# Sonic_Sandbox.net
KiCad netlist of a schematic drawn in Altium Designer
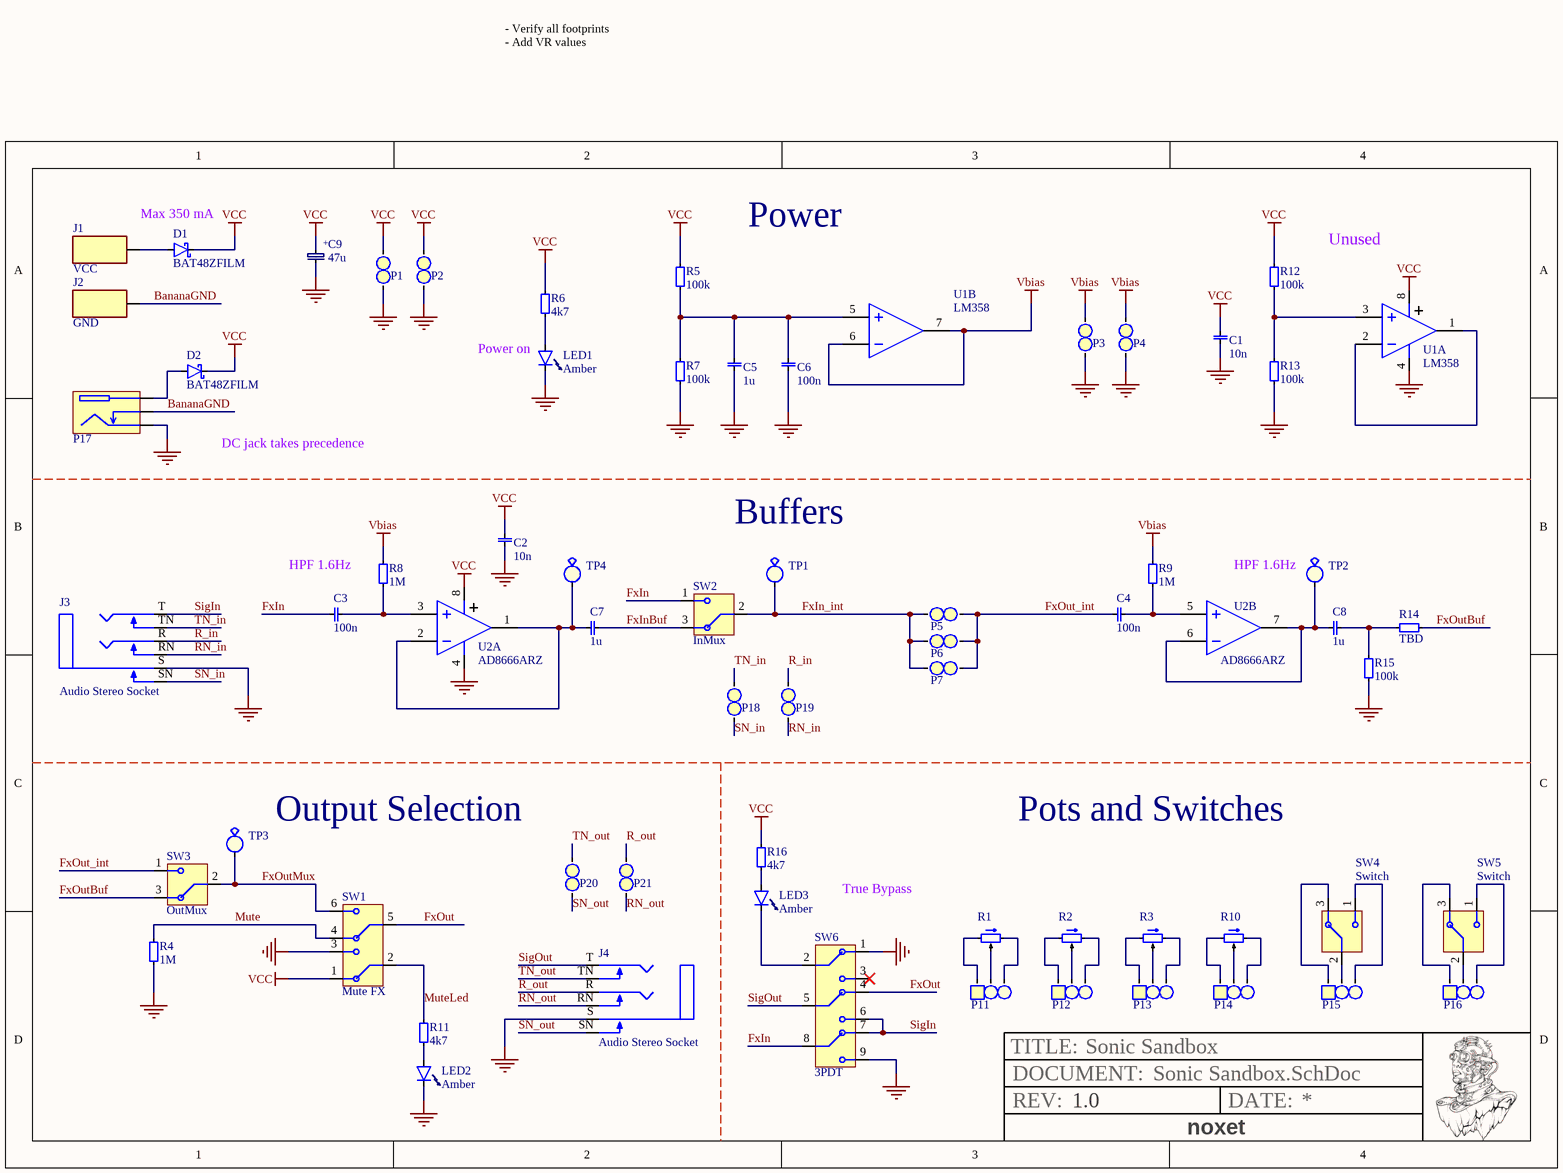
[diagram p0: Sonic Sandbox.SchDoc]

(export (version "E")
  (design (tool "Eeschema 10.0.6"))
  (components
    (comp (ref "C1")
      (value "10n")
      (footprint "0805, cap")
      (fields (field (name "Comment") "0805, capacitor"))
      (libsource (lib "jclib") (part "0805, capacitor"))
    )
    (comp (ref "C2")
      (value "10n")
      (footprint "0805, cap")
      (fields (field (name "Comment") "0805, capacitor"))
      (libsource (lib "jclib") (part "0805, capacitor"))
    )
    (comp (ref "C3")
      (value "100n")
      (footprint "0805, cap")
      (fields (field (name "Comment") "0805, capacitor"))
      (libsource (lib "jclib") (part "0805, capacitor"))
    )
    (comp (ref "C4")
      (value "100n")
      (footprint "0805, cap")
      (fields (field (name "Comment") "0805, capacitor"))
      (libsource (lib "jclib") (part "0805, capacitor"))
    )
    (comp (ref "C5")
      (value "1u")
      (footprint "0805, cap")
      (fields (field (name "Comment") "0805, capacitor"))
      (libsource (lib "jclib") (part "0805, capacitor"))
    )
    (comp (ref "C6")
      (value "100n")
      (footprint "0805, cap")
      (fields (field (name "Comment") "0805, capacitor"))
      (libsource (lib "jclib") (part "0805, capacitor"))
    )
    (comp (ref "C7")
      (value "1u")
      (footprint "0805, cap")
      (fields (field (name "Comment") "0805, capacitor"))
      (libsource (lib "jclib") (part "0805, capacitor"))
    )
    (comp (ref "C8")
      (value "1u")
      (footprint "0805, cap")
      (fields (field (name "Comment") "0805, capacitor"))
      (libsource (lib "jclib") (part "0805, capacitor"))
    )
    (comp (ref "C9")
      (value "47u")
      (footprint "Cap, SMD, Polar, 5.3x5.3mm")
      (description "Capacitor TH 2mm")
      (fields (field (name "Comment") "Capacitor, TH 2mm"))
      (libsource (lib "jclib") (part "Capacitor, TH 2mm"))
    )
    (comp (ref "D1")
      (value "BAT48ZFILM")
      (footprint "SOD123")
      (description "Rectifier Diode, Schottky, 1 Phase, 1 Element, 0.35A, 40V V(RRM), Silicon")
      (fields (field (name "MANUFACTURER") "STMicroelectronics"))
      (libsource (lib "jclib") (part "BAT48ZFILM"))
    )
    (comp (ref "D2")
      (value "BAT48ZFILM")
      (footprint "SOD123")
      (description "Rectifier Diode, Schottky, 1 Phase, 1 Element, 0.35A, 40V V(RRM), Silicon")
      (fields (field (name "MANUFACTURER") "STMicroelectronics"))
      (libsource (lib "jclib") (part "BAT48ZFILM"))
    )
    (comp (ref "J1")
      (value "VCC")
      (footprint "Banana Conn VCC")
      (description "Banana Connector 571-0100")
      (fields
        (field (name "MANUFACTURER_PART_NUMBER") "571-0100")
        (field (name "MOUSER PART NUMBER") "164-6218")
      )
      (libsource (lib "jclib") (part "Banana conn"))
    )
    (comp (ref "J2")
      (value "GND")
      (footprint "Banana Conn GND")
      (description "Banana Connector 571-0100")
      (fields
        (field (name "MANUFACTURER_PART_NUMBER") "571-0100")
        (field (name "MOUSER PART NUMBER") "164-6218")
      )
      (libsource (lib "jclib") (part "Banana conn"))
    )
    (comp (ref "J3")
      (value "Audio Stereo Socket")
      (footprint "6.3mm Audio Socket PCB")
      (libsource (lib "") (part "6.3mm Audio Socket_1"))
    )
    (comp (ref "J4")
      (value "Audio Stereo Socket")
      (footprint "6.3mm Audio Socket PCB")
      (libsource (lib "jclib") (part "6.3mm Audio Socket"))
    )
    (comp (ref "LED1") (value "Amber") (footprint "0805_led") (libsource (lib "jclib") (part "0805, LED")))
    (comp (ref "LED2") (value "Amber") (footprint "0805_led") (libsource (lib "jclib") (part "0805, LED")))
    (comp (ref "LED3") (value "Amber") (footprint "0805_led") (libsource (lib "jclib") (part "0805, LED")))
    (comp (ref "P1")
      (value "1x2 Pin Heade Straight")
      (footprint "padtwo_L")
      (description "2.54 mm, TH")
      (libsource (lib "jclib") (part "1x2 Pin Heade Straight"))
    )
    (comp (ref "P2")
      (value "1x2 Pin Heade Straight")
      (footprint "padtwo_L")
      (description "2.54 mm, TH")
      (libsource (lib "jclib") (part "1x2 Pin Heade Straight"))
    )
    (comp (ref "P3")
      (value "1x2 Pin Heade Straight")
      (footprint "padtwo_L")
      (description "2.54 mm, TH")
      (libsource (lib "jclib") (part "1x2 Pin Heade Straight"))
    )
    (comp (ref "P4")
      (value "1x2 Pin Heade Straight")
      (footprint "padtwo_L")
      (description "2.54 mm, TH")
      (libsource (lib "jclib") (part "1x2 Pin Heade Straight"))
    )
    (comp (ref "P5")
      (value "1x2 Pin Heade Straight")
      (footprint "padtwo_L")
      (description "2.54 mm, TH")
      (libsource (lib "jclib") (part "1x2 Pin Heade Straight"))
    )
    (comp (ref "P6")
      (value "1x2 Pin Heade Straight")
      (footprint "padtwo_L")
      (description "2.54 mm, TH")
      (libsource (lib "jclib") (part "1x2 Pin Heade Straight"))
    )
    (comp (ref "P7")
      (value "1x2 Pin Heade Straight")
      (footprint "padtwo_L")
      (description "2.54 mm, TH")
      (libsource (lib "jclib") (part "1x2 Pin Heade Straight"))
    )
    (comp (ref "P11")
      (value "1x3 Pin Header")
      (footprint "padThree_L")
      (description "2.54 mm")
      (libsource (lib "jclib") (part "1x3 Pin Header"))
    )
    (comp (ref "P12")
      (value "1x3 Pin Header")
      (footprint "padThree_L")
      (description "2.54 mm")
      (libsource (lib "jclib") (part "1x3 Pin Header"))
    )
    (comp (ref "P13")
      (value "1x3 Pin Header")
      (footprint "padThree_L")
      (description "2.54 mm")
      (libsource (lib "jclib") (part "1x3 Pin Header"))
    )
    (comp (ref "P14")
      (value "1x3 Pin Header")
      (footprint "padThree_L")
      (description "2.54 mm")
      (libsource (lib "jclib") (part "1x3 Pin Header"))
    )
    (comp (ref "P15")
      (value "1x3 Pin Header")
      (footprint "padThree_L")
      (description "2.54 mm")
      (libsource (lib "jclib") (part "1x3 Pin Header"))
    )
    (comp (ref "P16")
      (value "1x3 Pin Header")
      (footprint "padThree_L")
      (description "2.54 mm")
      (libsource (lib "jclib") (part "1x3 Pin Header"))
    )
    (comp (ref "P17")
      (value "Power socket")
      (footprint "DC Plug PCB")
      (libsource (lib "jclib") (part "Power socket"))
    )
    (comp (ref "P18")
      (value "1x2 Pin Heade Straight")
      (footprint "padtwo_L")
      (description "2.54 mm, TH")
      (libsource (lib "jclib") (part "1x2 Pin Heade Straight"))
    )
    (comp (ref "P19")
      (value "1x2 Pin Heade Straight")
      (footprint "padtwo_L")
      (description "2.54 mm, TH")
      (libsource (lib "jclib") (part "1x2 Pin Heade Straight"))
    )
    (comp (ref "P20")
      (value "1x2 Pin Heade Straight")
      (footprint "padtwo_L")
      (description "2.54 mm, TH")
      (libsource (lib "jclib") (part "1x2 Pin Heade Straight"))
    )
    (comp (ref "P21")
      (value "1x2 Pin Heade Straight")
      (footprint "padtwo_L")
      (description "2.54 mm, TH")
      (libsource (lib "jclib") (part "1x2 Pin Heade Straight"))
    )
    (comp (ref "R1")
      (value "Potentiometer")
      (footprint "RK09L_15mm")
      (libsource (lib "jclib") (part "Potentiometer"))
    )
    (comp (ref "R2")
      (value "Potentiometer")
      (footprint "RK09L_15mm")
      (libsource (lib "jclib") (part "Potentiometer"))
    )
    (comp (ref "R3")
      (value "Potentiometer")
      (footprint "RK09L_15mm")
      (libsource (lib "jclib") (part "Potentiometer"))
    )
    (comp (ref "R4")
      (value "1M")
      (footprint "0805")
      (fields (field (name "Comment") "General resistor"))
      (libsource (lib "jclib") (part "resistor"))
    )
    (comp (ref "R5")
      (value "100k")
      (footprint "0805")
      (fields (field (name "Comment") "General resistor"))
      (libsource (lib "jclib") (part "resistor"))
    )
    (comp (ref "R6")
      (value "4k7")
      (footprint "0805")
      (fields (field (name "Comment") "General resistor"))
      (libsource (lib "jclib") (part "resistor"))
    )
    (comp (ref "R7")
      (value "100k")
      (footprint "0805")
      (fields (field (name "Comment") "General resistor"))
      (libsource (lib "jclib") (part "resistor"))
    )
    (comp (ref "R8")
      (value "1M")
      (footprint "0805")
      (fields (field (name "Comment") "General resistor"))
      (libsource (lib "jclib") (part "resistor"))
    )
    (comp (ref "R9")
      (value "1M")
      (footprint "0805")
      (fields (field (name "Comment") "General resistor"))
      (libsource (lib "jclib") (part "resistor"))
    )
    (comp (ref "R10")
      (value "Potentiometer")
      (footprint "RK09L_15mm")
      (libsource (lib "jclib") (part "Potentiometer"))
    )
    (comp (ref "R11")
      (value "4k7")
      (footprint "0805")
      (fields (field (name "Comment") "General resistor"))
      (libsource (lib "jclib") (part "resistor"))
    )
    (comp (ref "R12")
      (value "100k")
      (footprint "0805")
      (fields (field (name "Comment") "General resistor"))
      (libsource (lib "jclib") (part "resistor"))
    )
    (comp (ref "R13")
      (value "100k")
      (footprint "0805")
      (fields (field (name "Comment") "General resistor"))
      (libsource (lib "jclib") (part "resistor"))
    )
    (comp (ref "R14")
      (value "TBD")
      (footprint "0805")
      (fields (field (name "Comment") "General resistor"))
      (libsource (lib "jclib") (part "resistor"))
    )
    (comp (ref "R15")
      (value "100k")
      (footprint "0805")
      (fields (field (name "Comment") "General resistor"))
      (libsource (lib "jclib") (part "resistor"))
    )
    (comp (ref "R16")
      (value "4k7")
      (footprint "0805")
      (fields (field (name "Comment") "General resistor"))
      (libsource (lib "jclib") (part "resistor"))
    )
    (comp (ref "SW1")
      (value "Mute FX")
      (footprint "SW_DPDT_MTS-202-A2")
      (description "Toggle switch DPDT")
      (libsource (lib "jclib") (part "Switch DPDT"))
    )
    (comp (ref "SW2")
      (value "InMux")
      (footprint "SW_SPDT_SMTS-102-A2")
      (description "Toggle switch SPDT")
      (libsource (lib "jclib") (part "Switch SPDT"))
    )
    (comp (ref "SW3")
      (value "OutMux")
      (footprint "SW_SPDT_SMTS-102-A2")
      (description "Toggle switch SPDT")
      (libsource (lib "jclib") (part "Switch SPDT"))
    )
    (comp (ref "SW4")
      (value "Switch")
      (footprint "SW_SPDT_SMTS-102-A2")
      (description "Toggle switch SPDT")
      (libsource (lib "") (part "Switch SPDT_1"))
    )
    (comp (ref "SW5")
      (value "Switch")
      (footprint "SW_SPDT_SMTS-102-A2")
      (description "Toggle switch SPDT")
      (libsource (lib "") (part "Switch SPDT_1"))
    )
    (comp (ref "SW6")
      (value "3PDT")
      (footprint "SW_3PDT_PBS-24-302")
      (description "Toggle switch 3PDT")
      (libsource (lib "jclib") (part "Switch 3PDT"))
    )
    (comp (ref "TP1")
      (value "Test Point")
      (footprint "TESTPOINT_SMD")
      (libsource (lib "jclib") (part "Test Point"))
    )
    (comp (ref "TP2")
      (value "Test Point")
      (footprint "TESTPOINT_SMD")
      (libsource (lib "jclib") (part "Test Point"))
    )
    (comp (ref "TP3")
      (value "Test Point")
      (footprint "TESTPOINT_SMD")
      (libsource (lib "jclib") (part "Test Point"))
    )
    (comp (ref "TP4")
      (value "Test Point")
      (footprint "TESTPOINT_SMD")
      (libsource (lib "jclib") (part "Test Point"))
    )
    (comp (ref "U1")
      (value "LM358")
      (footprint "SOIC8")
      (description "IC OPAMP GP 700KHZ 8SOIC")
      (fields
        (field (name "MANUFACTURER") "Texas Instruments")
        (field (name "MANUFACTURER PART NUMBER") "LM358DR")
      )
      (libsource (lib "jclib") (part "LM358DR"))
    )
    (comp (ref "U2")
      (value "AD8666ARZ")
      (footprint "SOIC8")
      (description "Operational Amplifier, 2 Func, 5000uV Offset-Max, CMOS, PDSO8")
      (fields (field (name "MANUFACTURER") "Analog Devices") (field (name "POWER") "No"))
      (libsource (lib "jclib") (part "AD8666ARZ"))
    )
  )
  (nets
    (net (code "1") (name "/BananaGND") (class "Default")
      (node (ref "J2") (pin "1") (pinfunction "1_1") (pintype "passive"))
      (node (ref "P17") (pin "3") (pinfunction "3_3") (pintype "passive"))
    )
    (net (code "2") (name "/FxIn") (class "Default")
      (node (ref "C3") (pin "2") (pinfunction "2_2") (pintype "passive"))
      (node (ref "SW2") (pin "1") (pinfunction "1_1") (pintype "passive"))
      (node (ref "SW6") (pin "8") (pinfunction "8_8") (pintype "passive"))
    )
    (net (code "3") (name "/FxInBuf") (class "Default")
      (node (ref "C7") (pin "1") (pinfunction "1_1") (pintype "passive"))
      (node (ref "SW2") (pin "3") (pinfunction "3_3") (pintype "passive"))
    )
    (net (code "4") (name "/FxIn_int") (class "Default")
      (node (ref "P5") (pin "2") (pinfunction "2_2") (pintype "passive"))
      (node (ref "P6") (pin "2") (pinfunction "2_2") (pintype "passive"))
      (node (ref "P7") (pin "2") (pinfunction "2_2") (pintype "passive"))
      (node (ref "SW2") (pin "2") (pinfunction "2_2") (pintype "passive"))
      (node (ref "TP1") (pin "0") (pinfunction "0_0") (pintype "passive"))
    )
    (net (code "5") (name "/FxOut") (class "Default")
      (node (ref "SW1") (pin "5") (pinfunction "5_5") (pintype "passive"))
      (node (ref "SW6") (pin "4") (pinfunction "4_4") (pintype "passive"))
    )
    (net (code "6") (name "/FxOutBuf") (class "Default")
      (node (ref "R14") (pin "1") (pinfunction "1_1") (pintype "passive"))
      (node (ref "SW3") (pin "3") (pinfunction "3_3") (pintype "passive"))
    )
    (net (code "7") (name "/FxOutMux") (class "Default")
      (node (ref "SW1") (pin "6") (pinfunction "6_6") (pintype "passive"))
      (node (ref "SW3") (pin "2") (pinfunction "2_2") (pintype "passive"))
      (node (ref "TP3") (pin "0") (pinfunction "0_0") (pintype "passive"))
    )
    (net (code "8") (name "/FxOut_int") (class "Default")
      (node (ref "C4") (pin "2") (pinfunction "2_2") (pintype "passive"))
      (node (ref "P5") (pin "1") (pinfunction "1_1") (pintype "passive"))
      (node (ref "P6") (pin "1") (pinfunction "1_1") (pintype "passive"))
      (node (ref "P7") (pin "1") (pinfunction "1_1") (pintype "passive"))
      (node (ref "SW3") (pin "1") (pinfunction "1_1") (pintype "passive"))
    )
    (net (code "9") (name "/Mute") (class "Default")
      (node (ref "R4") (pin "2") (pinfunction "2_2") (pintype "passive"))
      (node (ref "SW1") (pin "4") (pinfunction "4_4") (pintype "passive"))
    )
    (net (code "10") (name "/MuteLed") (class "Default")
      (node (ref "R11") (pin "2") (pinfunction "2_2") (pintype "passive"))
      (node (ref "SW1") (pin "2") (pinfunction "2_2") (pintype "passive"))
    )
    (net (code "11") (name "/RN_in") (class "Default")
      (node (ref "J3") (pin "RN") (pinfunction "~{R}_RN") (pintype "passive"))
      (node (ref "P19") (pin "2") (pinfunction "2_2") (pintype "passive"))
    )
    (net (code "12") (name "/RN_out") (class "Default")
      (node (ref "J4") (pin "RN") (pinfunction "~{R}_RN") (pintype "passive"))
      (node (ref "P21") (pin "2") (pinfunction "2_2") (pintype "passive"))
    )
    (net (code "13") (name "/R_in") (class "Default")
      (node (ref "J3") (pin "R") (pinfunction "R_R") (pintype "passive"))
      (node (ref "P19") (pin "1") (pinfunction "1_1") (pintype "passive"))
    )
    (net (code "14") (name "/R_out") (class "Default")
      (node (ref "J4") (pin "R") (pinfunction "R_R") (pintype "passive"))
      (node (ref "P21") (pin "1") (pinfunction "1_1") (pintype "passive"))
    )
    (net (code "15") (name "/SN_in") (class "Default")
      (node (ref "J3") (pin "SN") (pinfunction "~{S}_SN") (pintype "passive"))
      (node (ref "P18") (pin "2") (pinfunction "2_2") (pintype "passive"))
    )
    (net (code "16") (name "/SN_out") (class "Default")
      (node (ref "J4") (pin "SN") (pinfunction "~{S}_SN") (pintype "passive"))
      (node (ref "P20") (pin "2") (pinfunction "2_2") (pintype "passive"))
    )
    (net (code "17") (name "/SigIn") (class "Default")
      (node (ref "J3") (pin "T") (pinfunction "T_T") (pintype "passive"))
      (node (ref "SW6") (pin "6") (pinfunction "6_6") (pintype "passive"))
      (node (ref "SW6") (pin "7") (pinfunction "7_7") (pintype "passive"))
    )
    (net (code "18") (name "/SigOut") (class "Default")
      (node (ref "J4") (pin "T") (pinfunction "T_T") (pintype "passive"))
      (node (ref "SW6") (pin "5") (pinfunction "5_5") (pintype "passive"))
    )
    (net (code "19") (name "/TN_in") (class "Default")
      (node (ref "J3") (pin "TN") (pinfunction "~{T}_TN") (pintype "passive"))
      (node (ref "P18") (pin "1") (pinfunction "1_1") (pintype "passive"))
    )
    (net (code "20") (name "/TN_out") (class "Default")
      (node (ref "J4") (pin "TN") (pinfunction "~{T}_TN") (pintype "passive"))
      (node (ref "P20") (pin "1") (pinfunction "1_1") (pintype "passive"))
    )
    (net (code "21") (name "GND") (class "Default")
      (node (ref "C1") (pin "2") (pinfunction "2_2") (pintype "passive"))
      (node (ref "C2") (pin "2") (pinfunction "2_2") (pintype "passive"))
      (node (ref "C5") (pin "2") (pinfunction "2_2") (pintype "passive"))
      (node (ref "C6") (pin "2") (pinfunction "2_2") (pintype "passive"))
      (node (ref "C9") (pin "1") (pinfunction "1_1") (pintype "passive"))
      (node (ref "J3") (pin "S") (pinfunction "S_S") (pintype "passive"))
      (node (ref "J4") (pin "S") (pinfunction "S_S") (pintype "passive"))
      (node (ref "LED1") (pin "0") (pinfunction "Cathode_0") (pintype "passive"))
      (node (ref "LED2") (pin "0") (pinfunction "Cathode_0") (pintype "passive"))
      (node (ref "P1") (pin "2") (pinfunction "2_2") (pintype "passive"))
      (node (ref "P17") (pin "2") (pinfunction "2_2") (pintype "passive"))
      (node (ref "P2") (pin "2") (pinfunction "2_2") (pintype "passive"))
      (node (ref "P3") (pin "2") (pinfunction "2_2") (pintype "passive"))
      (node (ref "P4") (pin "2") (pinfunction "2_2") (pintype "passive"))
      (node (ref "R13") (pin "1") (pinfunction "1_1") (pintype "passive"))
      (node (ref "R15") (pin "2") (pinfunction "2_2") (pintype "passive"))
      (node (ref "R4") (pin "1") (pinfunction "1_1") (pintype "passive"))
      (node (ref "R7") (pin "1") (pinfunction "1_1") (pintype "passive"))
      (node (ref "SW1") (pin "3") (pinfunction "3_3") (pintype "passive"))
      (node (ref "SW6") (pin "1") (pinfunction "1_1") (pintype "passive"))
      (node (ref "SW6") (pin "9") (pinfunction "9_9") (pintype "passive"))
      (node (ref "U1") (pin "4") (pinfunction "V-_4") (pintype "passive"))
      (node (ref "U2") (pin "4") (pinfunction "V-_4") (pintype "passive"))
    )
    (net (code "22") (name "Net-(C8-Pad1)") (class "Default")
      (node (ref "C8") (pin "1") (pinfunction "1_1") (pintype "passive"))
      (node (ref "R14") (pin "2") (pinfunction "2_2") (pintype "passive"))
      (node (ref "R15") (pin "1") (pinfunction "1_1") (pintype "passive"))
    )
    (net (code "23") (name "Net-(D1-A)") (class "Default")
      (node (ref "D1") (pin "2") (pinfunction "A_2") (pintype "passive"))
      (node (ref "J1") (pin "1") (pinfunction "1_1") (pintype "passive"))
    )
    (net (code "24") (name "Net-(D2-A)") (class "Default")
      (node (ref "D2") (pin "2") (pinfunction "A_2") (pintype "passive"))
      (node (ref "P17") (pin "1") (pinfunction "1_1") (pintype "passive"))
    )
    (net (code "25") (name "Net-(LED1-Pad1)") (class "Default")
      (node (ref "LED1") (pin "1") (pinfunction "1_1") (pintype "passive"))
      (node (ref "R6") (pin "1") (pinfunction "1_1") (pintype "passive"))
    )
    (net (code "26") (name "Net-(LED2-Pad1)") (class "Default")
      (node (ref "LED2") (pin "1") (pinfunction "1_1") (pintype "passive"))
      (node (ref "R11") (pin "1") (pinfunction "1_1") (pintype "passive"))
    )
    (net (code "27") (name "Net-(LED3-Cathode)") (class "Default")
      (node (ref "LED3") (pin "0") (pinfunction "Cathode_0") (pintype "passive"))
      (node (ref "SW6") (pin "2") (pinfunction "2_2") (pintype "passive"))
    )
    (net (code "28") (name "Net-(LED3-Pad1)") (class "Default")
      (node (ref "LED3") (pin "1") (pinfunction "1_1") (pintype "passive"))
      (node (ref "R16") (pin "1") (pinfunction "1_1") (pintype "passive"))
    )
    (net (code "29") (name "Net-(P11-Pad1)") (class "Default")
      (node (ref "P11") (pin "1") (pinfunction "1_1") (pintype "passive"))
      (node (ref "R1") (pin "1") (pinfunction "1_1") (pintype "passive"))
    )
    (net (code "30") (name "Net-(P11-Pad2)") (class "Default")
      (node (ref "P11") (pin "2") (pinfunction "2_2") (pintype "passive"))
      (node (ref "R1") (pin "2") (pinfunction "2_2") (pintype "passive"))
    )
    (net (code "31") (name "Net-(P11-Pad3)") (class "Default")
      (node (ref "P11") (pin "3") (pinfunction "3_3") (pintype "passive"))
      (node (ref "R1") (pin "3") (pinfunction "3_3") (pintype "passive"))
    )
    (net (code "32") (name "Net-(P12-Pad1)") (class "Default")
      (node (ref "P12") (pin "1") (pinfunction "1_1") (pintype "passive"))
      (node (ref "R2") (pin "1") (pinfunction "1_1") (pintype "passive"))
    )
    (net (code "33") (name "Net-(P12-Pad2)") (class "Default")
      (node (ref "P12") (pin "2") (pinfunction "2_2") (pintype "passive"))
      (node (ref "R2") (pin "2") (pinfunction "2_2") (pintype "passive"))
    )
    (net (code "34") (name "Net-(P12-Pad3)") (class "Default")
      (node (ref "P12") (pin "3") (pinfunction "3_3") (pintype "passive"))
      (node (ref "R2") (pin "3") (pinfunction "3_3") (pintype "passive"))
    )
    (net (code "35") (name "Net-(P13-Pad1)") (class "Default")
      (node (ref "P13") (pin "1") (pinfunction "1_1") (pintype "passive"))
      (node (ref "R3") (pin "1") (pinfunction "1_1") (pintype "passive"))
    )
    (net (code "36") (name "Net-(P13-Pad2)") (class "Default")
      (node (ref "P13") (pin "2") (pinfunction "2_2") (pintype "passive"))
      (node (ref "R3") (pin "2") (pinfunction "2_2") (pintype "passive"))
    )
    (net (code "37") (name "Net-(P13-Pad3)") (class "Default")
      (node (ref "P13") (pin "3") (pinfunction "3_3") (pintype "passive"))
      (node (ref "R3") (pin "3") (pinfunction "3_3") (pintype "passive"))
    )
    (net (code "38") (name "Net-(P14-Pad1)") (class "Default")
      (node (ref "P14") (pin "1") (pinfunction "1_1") (pintype "passive"))
      (node (ref "R10") (pin "1") (pinfunction "1_1") (pintype "passive"))
    )
    (net (code "39") (name "Net-(P14-Pad2)") (class "Default")
      (node (ref "P14") (pin "2") (pinfunction "2_2") (pintype "passive"))
      (node (ref "R10") (pin "2") (pinfunction "2_2") (pintype "passive"))
    )
    (net (code "40") (name "Net-(P14-Pad3)") (class "Default")
      (node (ref "P14") (pin "3") (pinfunction "3_3") (pintype "passive"))
      (node (ref "R10") (pin "3") (pinfunction "3_3") (pintype "passive"))
    )
    (net (code "41") (name "Net-(P15-Pad1)") (class "Default")
      (node (ref "P15") (pin "1") (pinfunction "1_1") (pintype "passive"))
      (node (ref "SW4") (pin "3") (pinfunction "3_3") (pintype "passive"))
    )
    (net (code "42") (name "Net-(P15-Pad2)") (class "Default")
      (node (ref "P15") (pin "2") (pinfunction "2_2") (pintype "passive"))
      (node (ref "SW4") (pin "2") (pinfunction "2_2") (pintype "passive"))
    )
    (net (code "43") (name "Net-(P15-Pad3)") (class "Default")
      (node (ref "P15") (pin "3") (pinfunction "3_3") (pintype "passive"))
      (node (ref "SW4") (pin "1") (pinfunction "1_1") (pintype "passive"))
    )
    (net (code "44") (name "Net-(P16-Pad1)") (class "Default")
      (node (ref "P16") (pin "1") (pinfunction "1_1") (pintype "passive"))
      (node (ref "SW5") (pin "3") (pinfunction "3_3") (pintype "passive"))
    )
    (net (code "45") (name "Net-(P16-Pad2)") (class "Default")
      (node (ref "P16") (pin "2") (pinfunction "2_2") (pintype "passive"))
      (node (ref "SW5") (pin "2") (pinfunction "2_2") (pintype "passive"))
    )
    (net (code "46") (name "Net-(P16-Pad3)") (class "Default")
      (node (ref "P16") (pin "3") (pinfunction "3_3") (pintype "passive"))
      (node (ref "SW5") (pin "1") (pinfunction "1_1") (pintype "passive"))
    )
    (net (code "47") (name "Net-(U1A-IN+)") (class "Default")
      (node (ref "R12") (pin "1") (pinfunction "1_1") (pintype "passive"))
      (node (ref "R13") (pin "2") (pinfunction "2_2") (pintype "passive"))
      (node (ref "U1") (pin "3") (pinfunction "IN+_3") (pintype "passive"))
    )
    (net (code "48") (name "Net-(U1A-IN-)") (class "Default")
      (node (ref "U1") (pin "1") (pinfunction "OUT_1") (pintype "passive"))
      (node (ref "U1") (pin "2") (pinfunction "IN-_2") (pintype "passive"))
    )
    (net (code "49") (name "Net-(U1B-IN+)") (class "Default")
      (node (ref "C5") (pin "1") (pinfunction "1_1") (pintype "passive"))
      (node (ref "C6") (pin "1") (pinfunction "1_1") (pintype "passive"))
      (node (ref "R5") (pin "1") (pinfunction "1_1") (pintype "passive"))
      (node (ref "R7") (pin "2") (pinfunction "2_2") (pintype "passive"))
      (node (ref "U1") (pin "5") (pinfunction "IN+_5") (pintype "passive"))
    )
    (net (code "50") (name "Net-(U2A-IN+)") (class "Default")
      (node (ref "C3") (pin "1") (pinfunction "1_1") (pintype "passive"))
      (node (ref "R8") (pin "1") (pinfunction "1_1") (pintype "passive"))
      (node (ref "U2") (pin "3") (pinfunction "IN+_3") (pintype "passive"))
    )
    (net (code "51") (name "Net-(U2A-IN-)") (class "Default")
      (node (ref "C7") (pin "2") (pinfunction "2_2") (pintype "passive"))
      (node (ref "TP4") (pin "0") (pinfunction "0_0") (pintype "passive"))
      (node (ref "U2") (pin "1") (pinfunction "OUT_1") (pintype "passive"))
      (node (ref "U2") (pin "2") (pinfunction "IN-_2") (pintype "passive"))
    )
    (net (code "52") (name "Net-(U2B-IN+)") (class "Default")
      (node (ref "C4") (pin "1") (pinfunction "1_1") (pintype "passive"))
      (node (ref "R9") (pin "1") (pinfunction "1_1") (pintype "passive"))
      (node (ref "U2") (pin "5") (pinfunction "IN+_5") (pintype "passive"))
    )
    (net (code "53") (name "Net-(U2B-IN-)") (class "Default")
      (node (ref "C8") (pin "2") (pinfunction "2_2") (pintype "passive"))
      (node (ref "TP2") (pin "0") (pinfunction "0_0") (pintype "passive"))
      (node (ref "U2") (pin "6") (pinfunction "IN-_6") (pintype "passive"))
      (node (ref "U2") (pin "7") (pinfunction "OUT_7") (pintype "passive"))
    )
    (net (code "54") (name "VCC") (class "Default")
      (node (ref "C1") (pin "1") (pinfunction "1_1") (pintype "passive"))
      (node (ref "C2") (pin "1") (pinfunction "1_1") (pintype "passive"))
      (node (ref "C9") (pin "2") (pinfunction "2_2") (pintype "passive"))
      (node (ref "D1") (pin "1") (pinfunction "K_1") (pintype "passive"))
      (node (ref "D2") (pin "1") (pinfunction "K_1") (pintype "passive"))
      (node (ref "P1") (pin "1") (pinfunction "1_1") (pintype "passive"))
      (node (ref "P2") (pin "1") (pinfunction "1_1") (pintype "passive"))
      (node (ref "R12") (pin "2") (pinfunction "2_2") (pintype "passive"))
      (node (ref "R16") (pin "2") (pinfunction "2_2") (pintype "passive"))
      (node (ref "R5") (pin "2") (pinfunction "2_2") (pintype "passive"))
      (node (ref "R6") (pin "2") (pinfunction "2_2") (pintype "passive"))
      (node (ref "SW1") (pin "1") (pinfunction "1_1") (pintype "passive"))
      (node (ref "U1") (pin "8") (pinfunction "V+_8") (pintype "passive"))
      (node (ref "U2") (pin "8") (pinfunction "V+_8") (pintype "passive"))
    )
    (net (code "55") (name "Vbias") (class "Default")
      (node (ref "P3") (pin "1") (pinfunction "1_1") (pintype "passive"))
      (node (ref "P4") (pin "1") (pinfunction "1_1") (pintype "passive"))
      (node (ref "R8") (pin "2") (pinfunction "2_2") (pintype "passive"))
      (node (ref "R9") (pin "2") (pinfunction "2_2") (pintype "passive"))
      (node (ref "U1") (pin "6") (pinfunction "IN-_6") (pintype "passive"))
      (node (ref "U1") (pin "7") (pinfunction "OUT_7") (pintype "passive"))
    )
    (net (code "56") (name "unconnected-(SW6-Pad3)") (class "Default")
      (node (ref "SW6") (pin "3") (pinfunction "3_3") (pintype "passive+no_connect"))
    )
  )
)
